# scheme.net
KiCad netlist of a schematic drawn in Altium Designer
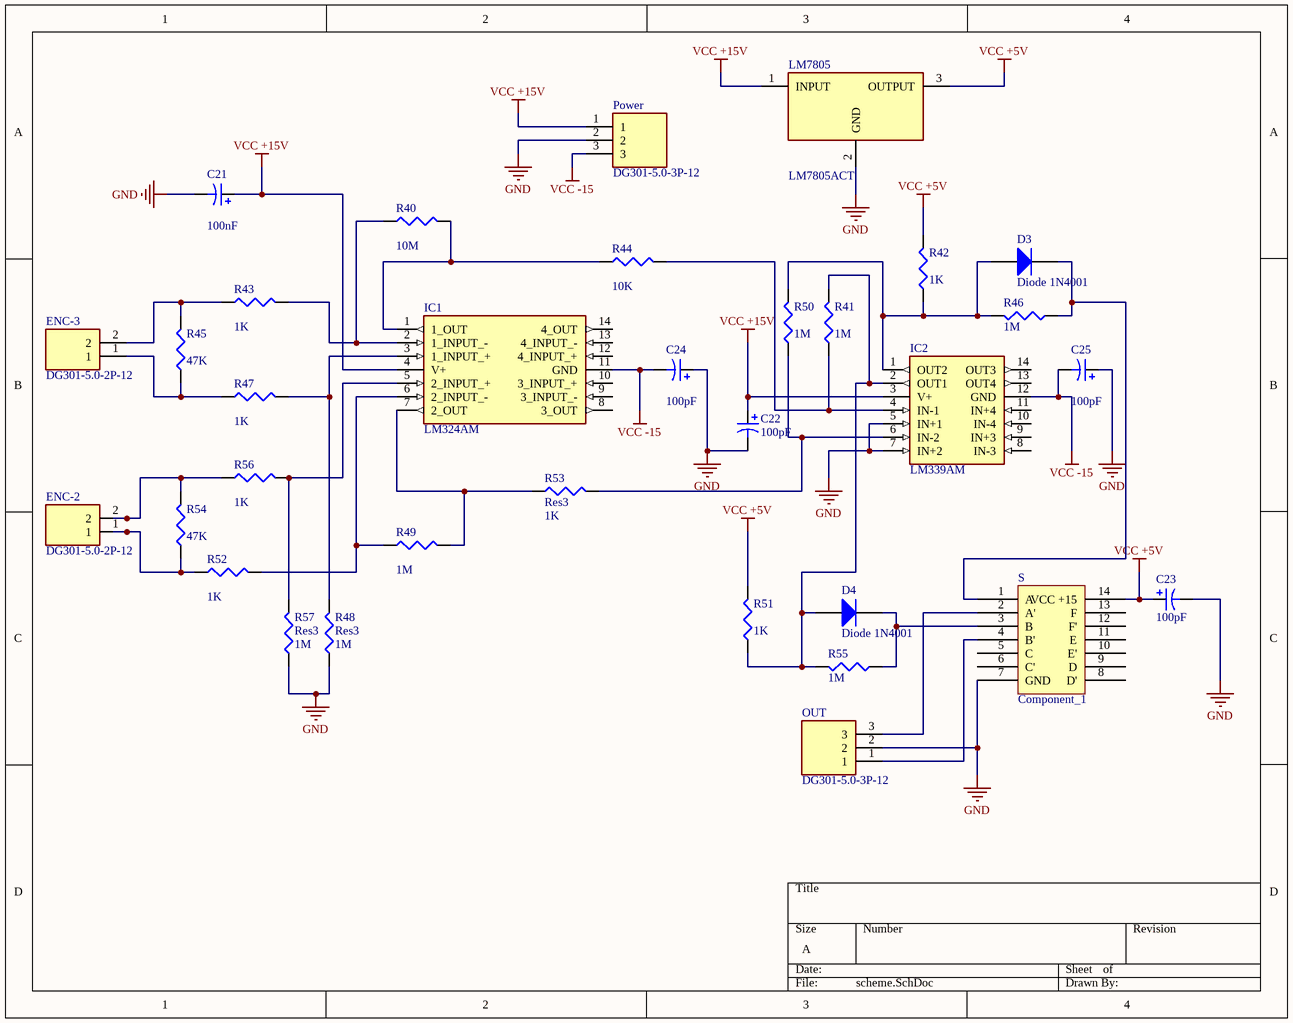
[diagram p0: scheme.SchDoc]

(export (version "E")
  (design (tool "Eeschema 10.0.6"))
  (components
    (comp (ref "C21")
      (value "100nF")
      (footprint "C1206")
      (description "Polarized Capacitor (Surface Mount)")
      (fields (field (name "Comment") "Cap Pol3") (field (name "PUBLISHER") "Altium Limited"))
      (libsource (lib "Miscellaneous Devices") (part "Cap Pol3"))
    )
    (comp (ref "C22")
      (value "100pF")
      (footprint "C1206")
      (description "Polarized Capacitor (Surface Mount)")
      (fields (field (name "Comment") "Cap Pol3") (field (name "PUBLISHER") "Altium Limited"))
      (libsource (lib "Miscellaneous Devices") (part "Cap Pol3"))
    )
    (comp (ref "C23")
      (value "100pF")
      (footprint "C1206")
      (description "Polarized Capacitor (Surface Mount)")
      (fields (field (name "Comment") "Cap Pol3") (field (name "PUBLISHER") "Altium Limited"))
      (libsource (lib "Miscellaneous Devices") (part "Cap Pol3"))
    )
    (comp (ref "C24")
      (value "100pF")
      (footprint "C1206")
      (description "Polarized Capacitor (Surface Mount)")
      (fields (field (name "Comment") "Cap Pol3") (field (name "PUBLISHER") "Altium Limited"))
      (libsource (lib "Miscellaneous Devices") (part "Cap Pol3"))
    )
    (comp (ref "C25")
      (value "100pF")
      (footprint "C1206")
      (description "Polarized Capacitor (Surface Mount)")
      (fields (field (name "Comment") "Cap Pol3") (field (name "PUBLISHER") "Altium Limited"))
      (libsource (lib "Miscellaneous Devices") (part "Cap Pol3"))
    )
    (comp (ref "D3")
      (value "Diode 1N4001")
      (footprint "SOT23_N")
      (description "1 Amp General Purpose Rectifier")
      (fields (field (name "PUBLISHER") "Altium Limited"))
      (libsource (lib "Miscellaneous Devices") (part "Diode 1N4001"))
    )
    (comp (ref "D4")
      (value "Diode 1N4001")
      (footprint "SOT23_N")
      (description "1 Amp General Purpose Rectifier")
      (fields (field (name "PUBLISHER") "Altium Limited"))
      (libsource (lib "Miscellaneous Devices") (part "Diode 1N4001"))
    )
    (comp (ref "ENC-2")
      (value "DG301-5.0-2P-12")
      (footprint "SamacSys:SHDR2W110P0X500_1X2_1000X760X1000P")
      (description "Connector")
      (libsource (lib "*") (part "DG301-5.0-2P-12"))
    )
    (comp (ref "ENC-3")
      (value "DG301-5.0-2P-12")
      (footprint "SamacSys:SHDR2W110P0X500_1X2_1000X760X1000P")
      (description "Connector")
      (libsource (lib "*") (part "DG301-5.0-2P-12"))
    )
    (comp (ref "IC1")
      (value "LM324AM")
      (footprint "SamacSys:SOIC127P600X175-14N")
      (description "Integrated Circuit")
      (fields (field (name "MOUSER PART NUMBER") "926-LM324AM") (field (name "RS PART NUMBER") "4713839"))
      (libsource (lib "*") (part "LM324AM"))
    )
    (comp (ref "IC2")
      (value "LM339AM")
      (footprint "SamacSys:SOIC127P600X175-14N")
      (description "Integrated Circuit")
      (fields (field (name "MOUSER PART NUMBER") "926-LM339AM") (field (name "RS PART NUMBER") "6364697"))
      (libsource (lib "*") (part "LM339AM"))
    )
    (comp (ref "LM7805")
      (value "LM7805ACT")
      (footprint "SamacSys:TO254P470X1016X2019-3P")
      (description "Integrated Circuit")
      (fields (field (name "MOUSER PART NUMBER") "512-LM7805ACT") (field (name "RS PART NUMBER") "8062839"))
      (libsource (lib "*") (part "LM7805ACT"))
    )
    (comp (ref "OUT")
      (value "DG301-5.0-3P-12")
      (footprint "SamacSys:SHDR3W110P0X500_1X3_1500X760X1000P")
      (description "Connector")
      (libsource (lib "*") (part "DG301-5.0-3P-12"))
    )
    (comp (ref "Power")
      (value "DG301-5.0-3P-12")
      (footprint "SamacSys:SHDR3W110P0X500_1X3_1500X760X1000P")
      (description "Connector")
      (libsource (lib "") (part "DG301-5.0-3P-12_1"))
    )
    (comp (ref "R40")
      (value "10M")
      (footprint "C1206")
      (description "Resistor")
      (fields (field (name "Comment") "Res3") (field (name "PUBLISHER") "Altium Limited"))
      (libsource (lib "Miscellaneous Devices") (part "Res3"))
    )
    (comp (ref "R41")
      (value "1M")
      (footprint "C1206")
      (description "Resistor")
      (fields (field (name "Comment") "Res3") (field (name "PUBLISHER") "Altium Limited"))
      (libsource (lib "Miscellaneous Devices") (part "Res3"))
    )
    (comp (ref "R42")
      (value "1K")
      (footprint "C1206")
      (description "Resistor")
      (fields (field (name "Comment") "Res3") (field (name "PUBLISHER") "Altium Limited"))
      (libsource (lib "Miscellaneous Devices") (part "Res3"))
    )
    (comp (ref "R43")
      (value "1K")
      (footprint "C1206")
      (description "Resistor")
      (fields (field (name "Comment") "Res3") (field (name "PUBLISHER") "Altium Limited"))
      (libsource (lib "Miscellaneous Devices") (part "Res3"))
    )
    (comp (ref "R44")
      (value "10K")
      (footprint "C1206")
      (description "Resistor")
      (fields (field (name "Comment") "Res3") (field (name "PUBLISHER") "Altium Limited"))
      (libsource (lib "Miscellaneous Devices") (part "Res3"))
    )
    (comp (ref "R45")
      (value "47K")
      (footprint "C1206")
      (description "Resistor")
      (fields (field (name "Comment") "Res3") (field (name "PUBLISHER") "Altium Limited"))
      (libsource (lib "Miscellaneous Devices") (part "Res3"))
    )
    (comp (ref "R46")
      (value "1M")
      (footprint "C1206")
      (description "Resistor")
      (fields (field (name "Comment") "Res3") (field (name "PUBLISHER") "Altium Limited"))
      (libsource (lib "Miscellaneous Devices") (part "Res3"))
    )
    (comp (ref "R47")
      (value "1K")
      (footprint "C1206")
      (description "Resistor")
      (fields (field (name "Comment") "Res3") (field (name "PUBLISHER") "Altium Limited"))
      (libsource (lib "Miscellaneous Devices") (part "Res3"))
    )
    (comp (ref "R48")
      (value "Res3")
      (footprint "C1206")
      (description "Resistor")
      (fields (field (name "ALTIUM_VALUE") "1M") (field (name "PUBLISHER") "Altium Limited"))
      (libsource (lib "Miscellaneous Devices") (part "Res3"))
    )
    (comp (ref "R49")
      (value "1M")
      (footprint "C1206")
      (description "Resistor")
      (fields (field (name "Comment") "Res3") (field (name "PUBLISHER") "Altium Limited"))
      (libsource (lib "Miscellaneous Devices") (part "Res3"))
    )
    (comp (ref "R50")
      (value "1M")
      (footprint "C1206")
      (description "Resistor")
      (fields (field (name "Comment") "Res3") (field (name "PUBLISHER") "Altium Limited"))
      (libsource (lib "Miscellaneous Devices") (part "Res3"))
    )
    (comp (ref "R51")
      (value "1K")
      (footprint "C1206")
      (description "Resistor")
      (fields (field (name "Comment") "Res3") (field (name "PUBLISHER") "Altium Limited"))
      (libsource (lib "Miscellaneous Devices") (part "Res3"))
    )
    (comp (ref "R52")
      (value "1K")
      (footprint "C1206")
      (description "Resistor")
      (fields (field (name "Comment") "Res3") (field (name "PUBLISHER") "Altium Limited"))
      (libsource (lib "Miscellaneous Devices") (part "Res3"))
    )
    (comp (ref "R53")
      (value "Res3")
      (footprint "C1206")
      (description "Resistor")
      (fields (field (name "ALTIUM_VALUE") "1K") (field (name "PUBLISHER") "Altium Limited"))
      (libsource (lib "Miscellaneous Devices") (part "Res3"))
    )
    (comp (ref "R54")
      (value "47K")
      (footprint "C1206")
      (description "Resistor")
      (fields (field (name "Comment") "Res3") (field (name "PUBLISHER") "Altium Limited"))
      (libsource (lib "Miscellaneous Devices") (part "Res3"))
    )
    (comp (ref "R55")
      (value "1M")
      (footprint "C1206")
      (description "Resistor")
      (fields (field (name "Comment") "Res3") (field (name "PUBLISHER") "Altium Limited"))
      (libsource (lib "Miscellaneous Devices") (part "Res3"))
    )
    (comp (ref "R56")
      (value "1K")
      (footprint "C1206")
      (description "Resistor")
      (fields (field (name "Comment") "Res3") (field (name "PUBLISHER") "Altium Limited"))
      (libsource (lib "Miscellaneous Devices") (part "Res3"))
    )
    (comp (ref "R57")
      (value "Res3")
      (footprint "C1206")
      (description "Resistor")
      (fields (field (name "ALTIUM_VALUE") "1M") (field (name "PUBLISHER") "Altium Limited"))
      (libsource (lib "Miscellaneous Devices") (part "Res3"))
    )
    (comp (ref "S")
      (value "Component_1")
      (footprint "SamacSys:SOIC127P600X175-14N")
      (libsource (lib "Schlib1") (part "Component_1"))
    )
  )
  (nets
    (net (code "1") (name "GND") (class "Default")
      (node (ref "C21") (pin "2") (pinfunction "2_2") (pintype "passive"))
      (node (ref "C22") (pin "2") (pinfunction "2_2") (pintype "passive"))
      (node (ref "C23") (pin "2") (pinfunction "2_2") (pintype "passive"))
      (node (ref "C24") (pin "1") (pinfunction "1_1") (pintype "passive"))
      (node (ref "C25") (pin "1") (pinfunction "1_1") (pintype "passive"))
      (node (ref "IC2") (pin "5") (pinfunction "IN+1_5") (pintype "input"))
      (node (ref "IC2") (pin "7") (pinfunction "IN+2_7") (pintype "input"))
      (node (ref "LM7805") (pin "2") (pinfunction "GND_2") (pintype "passive"))
      (node (ref "OUT") (pin "2") (pinfunction "2_2") (pintype "passive"))
      (node (ref "Power") (pin "2") (pinfunction "2_2") (pintype "passive"))
      (node (ref "R48") (pin "1") (pinfunction "1_1") (pintype "passive"))
      (node (ref "R57") (pin "1") (pinfunction "1_1") (pintype "passive"))
      (node (ref "S") (pin "7") (pinfunction "GND_7") (pintype "passive"))
    )
    (net (code "2") (name "Net-(D3-A)") (class "Default")
      (node (ref "D3") (pin "1") (pinfunction "A_1") (pintype "passive"))
      (node (ref "IC2") (pin "1") (pinfunction "OUT2_1") (pintype "output"))
      (node (ref "R42") (pin "1") (pinfunction "1_1") (pintype "passive"))
      (node (ref "R46") (pin "2") (pinfunction "2_2") (pintype "passive"))
      (node (ref "R50") (pin "2") (pinfunction "2_2") (pintype "passive"))
    )
    (net (code "3") (name "Net-(D3-K)") (class "Default")
      (node (ref "D3") (pin "2") (pinfunction "K_2") (pintype "passive"))
      (node (ref "R46") (pin "1") (pinfunction "1_1") (pintype "passive"))
      (node (ref "S") (pin "1") (pinfunction "A_1") (pintype "passive"))
    )
    (net (code "4") (name "Net-(D4-A)") (class "Default")
      (node (ref "D4") (pin "1") (pinfunction "A_1") (pintype "passive"))
      (node (ref "IC2") (pin "2") (pinfunction "OUT1_2") (pintype "output"))
      (node (ref "R41") (pin "2") (pinfunction "2_2") (pintype "passive"))
      (node (ref "R51") (pin "1") (pinfunction "1_1") (pintype "passive"))
      (node (ref "R55") (pin "2") (pinfunction "2_2") (pintype "passive"))
    )
    (net (code "5") (name "Net-(D4-K)") (class "Default")
      (node (ref "D4") (pin "2") (pinfunction "K_2") (pintype "passive"))
      (node (ref "R55") (pin "1") (pinfunction "1_1") (pintype "passive"))
      (node (ref "S") (pin "3") (pinfunction "B_3") (pintype "passive"))
    )
    (net (code "6") (name "Net-(ENC-2-Pad1)") (class "Default")
      (node (ref "ENC-2") (pin "1") (pinfunction "1_1") (pintype "passive"))
      (node (ref "R52") (pin "1") (pinfunction "1_1") (pintype "passive"))
      (node (ref "R54") (pin "1") (pinfunction "1_1") (pintype "passive"))
    )
    (net (code "7") (name "Net-(ENC-2-Pad2)") (class "Default")
      (node (ref "ENC-2") (pin "2") (pinfunction "2_2") (pintype "passive"))
      (node (ref "R54") (pin "2") (pinfunction "2_2") (pintype "passive"))
      (node (ref "R56") (pin "1") (pinfunction "1_1") (pintype "passive"))
    )
    (net (code "8") (name "Net-(ENC-3-Pad1)") (class "Default")
      (node (ref "ENC-3") (pin "1") (pinfunction "1_1") (pintype "passive"))
      (node (ref "R45") (pin "1") (pinfunction "1_1") (pintype "passive"))
      (node (ref "R47") (pin "1") (pinfunction "1_1") (pintype "passive"))
    )
    (net (code "9") (name "Net-(ENC-3-Pad2)") (class "Default")
      (node (ref "ENC-3") (pin "2") (pinfunction "2_2") (pintype "passive"))
      (node (ref "R43") (pin "1") (pinfunction "1_1") (pintype "passive"))
      (node (ref "R45") (pin "2") (pinfunction "2_2") (pintype "passive"))
    )
    (net (code "10") (name "Net-(IC1-1_INPUT_+)") (class "Default")
      (node (ref "IC1") (pin "3") (pinfunction "1_INPUT_+_3") (pintype "input"))
      (node (ref "R47") (pin "2") (pinfunction "2_2") (pintype "passive"))
      (node (ref "R48") (pin "2") (pinfunction "2_2") (pintype "passive"))
    )
    (net (code "11") (name "Net-(IC1-1_INPUT_-)") (class "Default")
      (node (ref "IC1") (pin "2") (pinfunction "1_INPUT_-_2") (pintype "input"))
      (node (ref "R40") (pin "1") (pinfunction "1_1") (pintype "passive"))
      (node (ref "R43") (pin "2") (pinfunction "2_2") (pintype "passive"))
    )
    (net (code "12") (name "Net-(IC1-1_OUT)") (class "Default")
      (node (ref "IC1") (pin "1") (pinfunction "1_OUT_1") (pintype "output"))
      (node (ref "R40") (pin "2") (pinfunction "2_2") (pintype "passive"))
      (node (ref "R44") (pin "1") (pinfunction "1_1") (pintype "passive"))
    )
    (net (code "13") (name "Net-(IC1-2_INPUT_+)") (class "Default")
      (node (ref "IC1") (pin "5") (pinfunction "2_INPUT_+_5") (pintype "input"))
      (node (ref "R56") (pin "2") (pinfunction "2_2") (pintype "passive"))
      (node (ref "R57") (pin "2") (pinfunction "2_2") (pintype "passive"))
    )
    (net (code "14") (name "Net-(IC1-2_INPUT_-)") (class "Default")
      (node (ref "IC1") (pin "6") (pinfunction "2_INPUT_-_6") (pintype "input"))
      (node (ref "R49") (pin "1") (pinfunction "1_1") (pintype "passive"))
      (node (ref "R52") (pin "2") (pinfunction "2_2") (pintype "passive"))
    )
    (net (code "15") (name "Net-(IC1-2_OUT)") (class "Default")
      (node (ref "IC1") (pin "7") (pinfunction "2_OUT_7") (pintype "output"))
      (node (ref "R49") (pin "2") (pinfunction "2_2") (pintype "passive"))
      (node (ref "R53") (pin "1") (pinfunction "1_1") (pintype "passive"))
    )
    (net (code "16") (name "Net-(IC2-IN-1)") (class "Default")
      (node (ref "IC2") (pin "4") (pinfunction "IN-1_4") (pintype "input"))
      (node (ref "R41") (pin "1") (pinfunction "1_1") (pintype "passive"))
      (node (ref "R44") (pin "2") (pinfunction "2_2") (pintype "passive"))
    )
    (net (code "17") (name "Net-(IC2-IN-2)") (class "Default")
      (node (ref "IC2") (pin "6") (pinfunction "IN-2_6") (pintype "input"))
      (node (ref "R50") (pin "1") (pinfunction "1_1") (pintype "passive"))
      (node (ref "R53") (pin "2") (pinfunction "2_2") (pintype "passive"))
    )
    (net (code "18") (name "Net-(S-A')") (class "Default")
      (node (ref "OUT") (pin "3") (pinfunction "3_3") (pintype "passive"))
      (node (ref "S") (pin "2") (pinfunction "A'_2") (pintype "passive"))
    )
    (net (code "19") (name "Net-(S-B')") (class "Default")
      (node (ref "OUT") (pin "1") (pinfunction "1_1") (pintype "passive"))
      (node (ref "S") (pin "4") (pinfunction "B'_4") (pintype "passive"))
    )
    (net (code "20") (name "VCC +5V") (class "Default")
      (node (ref "C23") (pin "1") (pinfunction "1_1") (pintype "passive"))
      (node (ref "LM7805") (pin "3") (pinfunction "OUTPUT_3") (pintype "passive"))
      (node (ref "R42") (pin "2") (pinfunction "2_2") (pintype "passive"))
      (node (ref "R51") (pin "2") (pinfunction "2_2") (pintype "passive"))
      (node (ref "S") (pin "14") (pinfunction "VCC_+15_14") (pintype "passive"))
    )
    (net (code "21") (name "VCC +15V") (class "Default")
      (node (ref "C21") (pin "1") (pinfunction "1_1") (pintype "passive"))
      (node (ref "C22") (pin "1") (pinfunction "1_1") (pintype "passive"))
      (node (ref "IC1") (pin "4") (pinfunction "V+_4") (pintype "passive"))
      (node (ref "IC2") (pin "3") (pinfunction "V+_3") (pintype "passive"))
      (node (ref "LM7805") (pin "1") (pinfunction "INPUT_1") (pintype "passive"))
      (node (ref "Power") (pin "1") (pinfunction "1_1") (pintype "passive"))
    )
    (net (code "22") (name "VCC -15") (class "Default")
      (node (ref "C24") (pin "2") (pinfunction "2_2") (pintype "passive"))
      (node (ref "C25") (pin "2") (pinfunction "2_2") (pintype "passive"))
      (node (ref "IC1") (pin "11") (pinfunction "GND_11") (pintype "power_in"))
      (node (ref "IC2") (pin "12") (pinfunction "GND_12") (pintype "power_in"))
      (node (ref "Power") (pin "3") (pinfunction "3_3") (pintype "passive"))
    )
    (net (code "23") (name "unconnected-(IC1-3_INPUT_+-Pad10)") (class "Default")
      (node (ref "IC1") (pin "10") (pinfunction "3_INPUT_+_10") (pintype "input"))
    )
    (net (code "24") (name "unconnected-(IC1-3_INPUT_--Pad9)") (class "Default")
      (node (ref "IC1") (pin "9") (pinfunction "3_INPUT_-_9") (pintype "input"))
    )
    (net (code "25") (name "unconnected-(IC1-3_OUT-Pad8)") (class "Default")
      (node (ref "IC1") (pin "8") (pinfunction "3_OUT_8") (pintype "output"))
    )
    (net (code "26") (name "unconnected-(IC1-4_INPUT_+-Pad12)") (class "Default")
      (node (ref "IC1") (pin "12") (pinfunction "4_INPUT_+_12") (pintype "input"))
    )
    (net (code "27") (name "unconnected-(IC1-4_INPUT_--Pad13)") (class "Default")
      (node (ref "IC1") (pin "13") (pinfunction "4_INPUT_-_13") (pintype "input"))
    )
    (net (code "28") (name "unconnected-(IC1-4_OUT-Pad14)") (class "Default")
      (node (ref "IC1") (pin "14") (pinfunction "4_OUT_14") (pintype "output"))
    )
    (net (code "29") (name "unconnected-(IC2-IN+3-Pad9)") (class "Default")
      (node (ref "IC2") (pin "9") (pinfunction "IN+3_9") (pintype "input"))
    )
    (net (code "30") (name "unconnected-(IC2-IN+4-Pad11)") (class "Default")
      (node (ref "IC2") (pin "11") (pinfunction "IN+4_11") (pintype "input"))
    )
    (net (code "31") (name "unconnected-(IC2-IN-3-Pad8)") (class "Default")
      (node (ref "IC2") (pin "8") (pinfunction "IN-3_8") (pintype "input"))
    )
    (net (code "32") (name "unconnected-(IC2-IN-4-Pad10)") (class "Default")
      (node (ref "IC2") (pin "10") (pinfunction "IN-4_10") (pintype "input"))
    )
    (net (code "33") (name "unconnected-(IC2-OUT3-Pad14)") (class "Default")
      (node (ref "IC2") (pin "14") (pinfunction "OUT3_14") (pintype "output"))
    )
    (net (code "34") (name "unconnected-(IC2-OUT4-Pad13)") (class "Default")
      (node (ref "IC2") (pin "13") (pinfunction "OUT4_13") (pintype "output"))
    )
    (net (code "35") (name "unconnected-(S-C'-Pad6)") (class "Default")
      (node (ref "S") (pin "6") (pinfunction "C'_6") (pintype "passive"))
    )
    (net (code "36") (name "unconnected-(S-C-Pad5)") (class "Default")
      (node (ref "S") (pin "5") (pinfunction "C_5") (pintype "passive"))
    )
    (net (code "37") (name "unconnected-(S-D'-Pad8)") (class "Default")
      (node (ref "S") (pin "8") (pinfunction "D'_8") (pintype "passive"))
    )
    (net (code "38") (name "unconnected-(S-D-Pad9)") (class "Default")
      (node (ref "S") (pin "9") (pinfunction "D_9") (pintype "passive"))
    )
    (net (code "39") (name "unconnected-(S-E'-Pad10)") (class "Default")
      (node (ref "S") (pin "10") (pinfunction "E'_10") (pintype "passive"))
    )
    (net (code "40") (name "unconnected-(S-E-Pad11)") (class "Default")
      (node (ref "S") (pin "11") (pinfunction "E_11") (pintype "passive"))
    )
    (net (code "41") (name "unconnected-(S-F'-Pad12)") (class "Default")
      (node (ref "S") (pin "12") (pinfunction "F'_12") (pintype "passive"))
    )
    (net (code "42") (name "unconnected-(S-F-Pad13)") (class "Default")
      (node (ref "S") (pin "13") (pinfunction "F_13") (pintype "passive"))
    )
  )
)
